# lp4200.net
KiCad netlist of a schematic drawn in Altium Designer
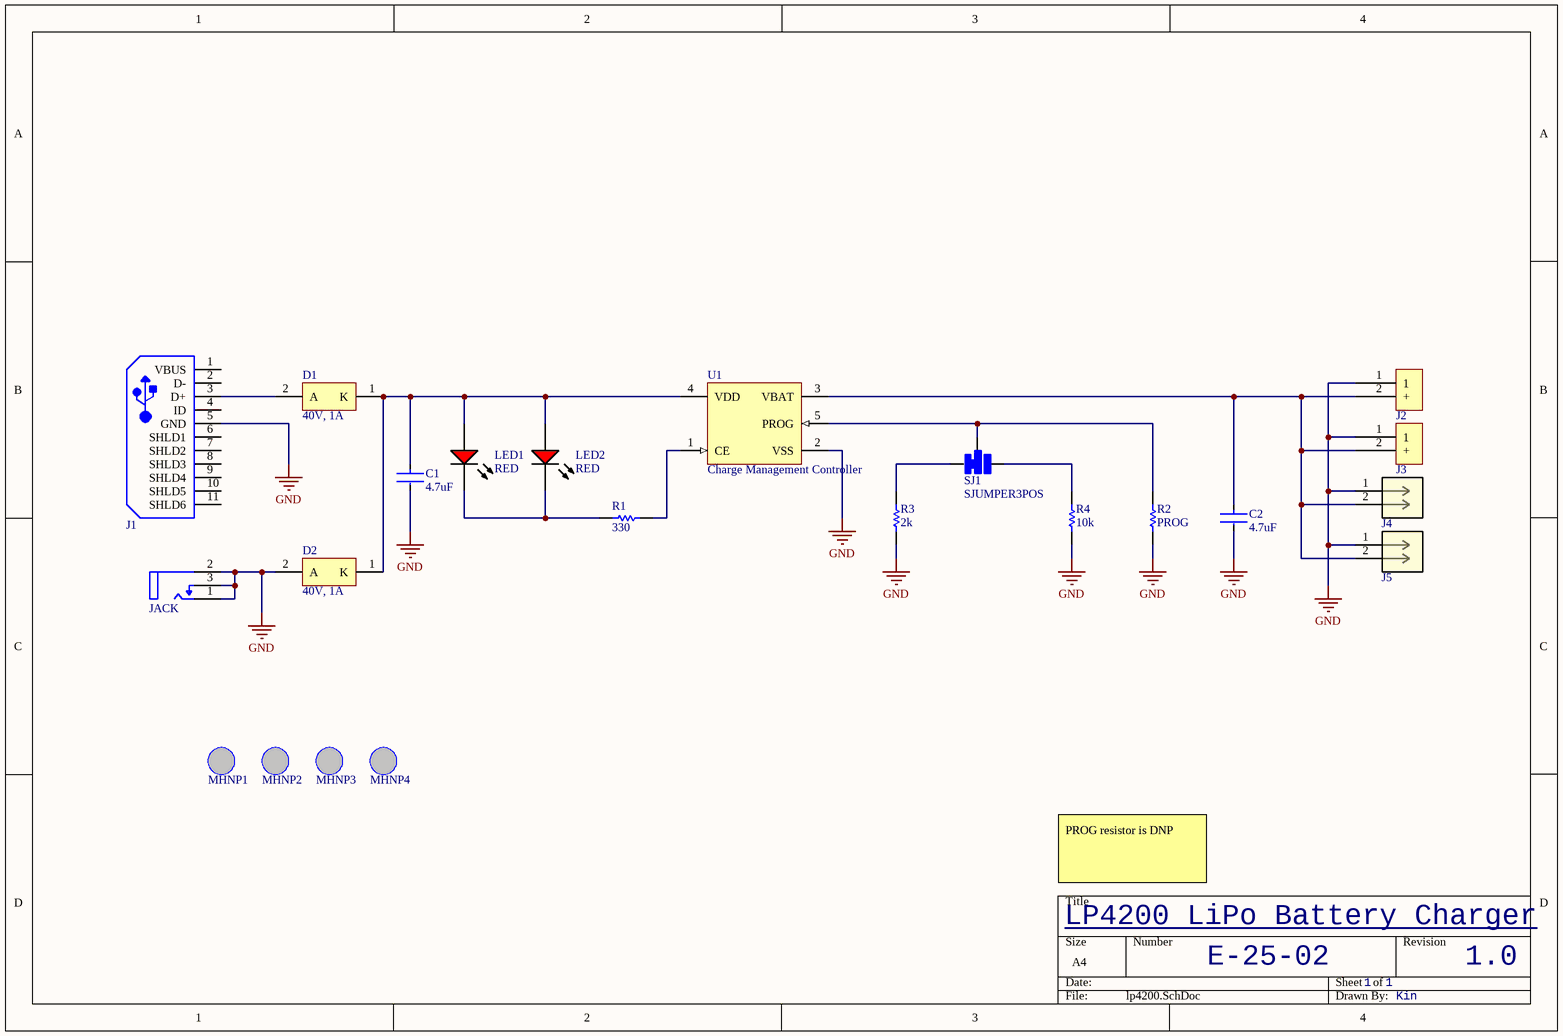
[diagram p0: lp4200.SchDoc]

(export (version "E")
  (design (tool "Eeschema 10.0.6"))
  (components
    (comp (ref "C1")
      (value "4.7uF")
      (footprint "FP-CC0805-0_85-MFG")
      (description "4.7µF ±10% 6.3V Ceramic Capacitor X7R 0805 (2012 Metric)")
      (fields (field (name "MANUFACTURER") "Yageo") (field (name "TOLERANCE") "0.1"))
      (libsource (lib "lp4200") (part "CAP CER 4.7UF 6.3V X7R 0805"))
    )
    (comp (ref "C2")
      (value "4.7uF")
      (footprint "FP-CC0805-0_85-MFG")
      (description "4.7µF ±10% 6.3V Ceramic Capacitor X7R 0805 (2012 Metric)")
      (fields (field (name "MANUFACTURER") "Yageo") (field (name "TOLERANCE") "0.1"))
      (libsource (lib "lp4200") (part "CAP CER 4.7UF 6.3V X7R 0805"))
    )
    (comp (ref "D1")
      (value "40V, 1A")
      (footprint "ONSC-SMA-2-403D-02_V")
      (description "Schottky Power Rectifier, 2-Pin SMA, Pb-Free, Cut Tape, Diode Schottky 40V 1A Surface Mount SMA")
      (fields (field (name "PARTNUMBER") "MBRA140T3G") (field (name "MANUFACTURER") "ON Semiconductor"))
      (libsource (lib "lp4200") (part "DIODE SCHOTTKY 40V 1A SMA"))
    )
    (comp (ref "D2")
      (value "40V, 1A")
      (footprint "ONSC-SMA-2-403D-02_V")
      (description "Schottky Power Rectifier, 2-Pin SMA, Pb-Free, Cut Tape, Diode Schottky 40V 1A Surface Mount SMA")
      (fields (field (name "PARTNUMBER") "MBRA140T3G") (field (name "MANUFACTURER") "ON Semiconductor"))
      (libsource (lib "lp4200") (part "DIODE SCHOTTKY 40V 1A SMA"))
    )
    (comp (ref "J1")
      (value "47346-0001")
      (footprint "MOLX-47346-0001-5_V")
      (description "Micro-USB B Receptacle with Flange, -30 to 85 degC, 5-Pin SMD, RoHS, Tape and Reel")
      (fields (field (name "MANUFACTURER") "Molex"))
      (libsource (lib "lp4200") (part "CONN RCPT USB2.0 MICRO B SMD R/A"))
    )
    (comp (ref "J2")
      (value "CONN HEADER R/A 2POS 5.08MM")
      (footprint "1-179276-2")
      (description "Connector Header Through Hole, Right Angle 2 position 0.200\" (5.08mm)")
      (fields
        (field (name "MANUFACTURER") "TE Connectivity AMP Connectors")
        (field (name "MANUFACTURER PART NUMBER") "1-179276-2")
      )
      (libsource (lib "lp4200") (part "CONN HEADER R/A 2POS 5.08MM"))
    )
    (comp (ref "J3")
      (value "CONN HEADER R/A 2POS 5.08MM")
      (footprint "1-179276-2")
      (description "Connector Header Through Hole, Right Angle 2 position 0.200\" (5.08mm)")
      (fields
        (field (name "MANUFACTURER") "TE Connectivity AMP Connectors")
        (field (name "MANUFACTURER PART NUMBER") "1-179276-2")
      )
      (libsource (lib "lp4200") (part "CONN HEADER R/A 2POS 5.08MM"))
    )
    (comp (ref "J4")
      (value "2 POS VERT HEADER 0.100\"")
      (footprint "2Pins_AMP")
      (description "Connector Header Through Hole 2 position")
      (fields
        (field (name "MANUFACTURER PART NUMBER") "67997-402HLF")
        (field (name "MANUFACTURER") "Amphenol ICC (FCI)")
        (field (name "COPYRIGHT") "Copyright (C) 2018 Accelerated Designs. All rights reserved")
      )
      (libsource (lib "lp4200") (part "CONN HEADER VERT 2POS 0.100{dblquote}"))
    )
    (comp (ref "J5")
      (value "2 POS VERT HEADER 0.100\"")
      (footprint "2Pins_AMP")
      (description "Connector Header Through Hole 2 position")
      (fields
        (field (name "MANUFACTURER PART NUMBER") "67997-402HLF")
        (field (name "MANUFACTURER") "Amphenol ICC (FCI)")
        (field (name "COPYRIGHT") "Copyright (C) 2018 Accelerated Designs. All rights reserved")
      )
      (libsource (lib "lp4200") (part "CONN HEADER VERT 2POS 0.100{dblquote}"))
    )
    (comp (ref "JACK")
      (value "CONN PWR JACK 2.1X5.5MM SOLDER")
      (footprint "FP-RASM722PTR13X-MFG")
      (description "Power Barrel Connector Jack 2.10mm ID (0.083\"), 5.50mm OD (0.217\") Surface Mount, Right Angle")
      (fields
        (field (name "MANUFACTURER") "Switchcraft")
        (field (name "MANUFACTURER PART NUMBER") "RASM722PTR13X")
      )
      (libsource (lib "lp4200") (part "CONN PWR JACK 2.1X5.5MM SOLDER"))
    )
    (comp (ref "LED1")
      (value "RED")
      (footprint "VISH-TLMS1000_V")
      (description "Low Current LED, 40 mW, 1.8 V, -40 to 100 degC, 2-Pin SMD (0603), RoHS, Tape and Reel")
      (fields
        (field (name "MANUFACTURER") "Vishay")
        (field (name "MANUFACTURER PART NUMBER") "TLMS1000-GS08")
      )
      (libsource (lib "lp4200") (part "LED RED 0603 SMD"))
    )
    (comp (ref "LED2")
      (value "RED")
      (footprint "VISH-TLMS1000_V")
      (description "Low Current LED, 40 mW, 1.8 V, -40 to 100 degC, 2-Pin SMD (0603), RoHS, Tape and Reel")
      (fields
        (field (name "MANUFACTURER") "Vishay")
        (field (name "MANUFACTURER PART NUMBER") "TLMS1000-GS08")
      )
      (libsource (lib "lp4200") (part "LED RED 0603 SMD"))
    )
    (comp (ref "MHNP1")
      (value "Mounting Hole Non-Plated 3.2mm")
      (footprint "MTHNP3P2MM")
      (description "Mounting Hole Non-Plated 3.2 mm drill hole")
      (libsource (lib "lp4200") (part "MTHNP3P2MM"))
    )
    (comp (ref "MHNP2")
      (value "Mounting Hole Non-Plated 3.2mm")
      (footprint "MTHNP3P2MM")
      (description "Mounting Hole Non-Plated 3.2 mm drill hole")
      (libsource (lib "lp4200") (part "MTHNP3P2MM"))
    )
    (comp (ref "MHNP3")
      (value "Mounting Hole Non-Plated 3.2mm")
      (footprint "MTHNP3P2MM")
      (description "Mounting Hole Non-Plated 3.2 mm drill hole")
      (libsource (lib "lp4200") (part "MTHNP3P2MM"))
    )
    (comp (ref "MHNP4")
      (value "Mounting Hole Non-Plated 3.2mm")
      (footprint "MTHNP3P2MM")
      (description "Mounting Hole Non-Plated 3.2 mm drill hole")
      (libsource (lib "lp4200") (part "MTHNP3P2MM"))
    )
    (comp (ref "R1")
      (value "330")
      (footprint "RESC2013X50X30NL20T20")
      (description "330 Ohms ±1% 0.125W, 1/8W Chip Resistor 0805 (2012 Metric) Automotive AEC-Q200 Thick Film")
      (fields
        (field (name "MANUFACTURER") "Vishay")
        (field (name "MANUFACTURER PART NUMBER") "CRCW0805330RFKEA")
      )
      (libsource (lib "lp4200") (part "RES SMD 330 OHM 1% 1/8W 0805"))
    )
    (comp (ref "R2")
      (value "PROG")
      (footprint "VISH-A1-2_V2")
      (fields
        (field (name "TOLERANCE") "+/-5%")
        (field (name "POWER") "2 W")
        (field (name "PARTNUMBER") "PR02000206202JA100")
      )
      (libsource (lib "lp4200") (part "RES 62K OHM 2W 5% AXIAL"))
    )
    (comp (ref "R3")
      (value "2k")
      (footprint "RESC2013X70X40ML20T20")
      (description "2 kOhms ±5% 0.125W, 1/8W Chip Resistor 0805 (2012 Metric) Automotive AEC-Q200 Thick Film")
      (fields
        (field (name "MANUFACTURER") "Panasonic")
        (field (name "MANUFACTURER PART NUMBER") "ERJ-6GEYJ202V")
      )
      (libsource (lib "lp4200") (part "RES SMD 2K OHM 5% 1/8W 0805"))
    )
    (comp (ref "R4")
      (value "10k")
      (footprint "RESC2013X70X40ML20T20")
      (description "10 kOhms ±1% 0.125W, 1/8W Chip Resistor 0805 (2012 Metric) Automotive AEC-Q200 Thick Film")
      (fields
        (field (name "MANUFACTURER") "Panasonic")
        (field (name "MANUFACTURER PART NUMBER") "ERJ-6ENF1002V")
      )
      (libsource (lib "lp4200") (part "RES SMD 10K OHM 1% 1/8W 0805"))
    )
    (comp (ref "SJ1")
      (value "SJUMPER3POS")
      (footprint "SJUMPER3POS-Footprint-1")
      (description "Solder jumper 3 pads and pins")
      (libsource (lib "lp4200") (part "SJUMPER3POS"))
    )
    (comp (ref "U1")
      (value "Charge Management Controller")
      (footprint "SOT-23-OT5_M")
      (fields
        (field (name "MANUFACTURER") "Microchip")
        (field (name "MANUFACTURER PART NUMBER") "MCP73811T-420I/OT")
      )
      (libsource (lib "lp4200") (part "IC LI-ION/LI-POLY CTRLR SOT23-5"))
    )
  )
  (nets
    (net (code "1") (name "GND") (class "Default")
      (node (ref "C1") (pin "2") (pinfunction "2_2") (pintype "passive"))
      (node (ref "C2") (pin "2") (pinfunction "2_2") (pintype "passive"))
      (node (ref "D2") (pin "2") (pinfunction "A_2") (pintype "passive"))
      (node (ref "J1") (pin "5") (pinfunction "GND_5") (pintype "passive"))
      (node (ref "J2") (pin "1") (pinfunction "1_1") (pintype "passive"))
      (node (ref "J3") (pin "1") (pinfunction "1_1") (pintype "passive"))
      (node (ref "J4") (pin "1") (pinfunction "1_1") (pintype "passive"))
      (node (ref "J5") (pin "1") (pinfunction "1_1") (pintype "passive"))
      (node (ref "JACK") (pin "1") (pinfunction "TIP_TERMINAL(CENTER_PIN)_1") (pintype "passive"))
      (node (ref "JACK") (pin "2") (pinfunction "SLEEVE_TERMINAL_2") (pintype "passive"))
      (node (ref "JACK") (pin "3") (pinfunction "SHUNT_TERMINAL_3") (pintype "passive"))
      (node (ref "R2") (pin "1") (pinfunction "1_1") (pintype "passive"))
      (node (ref "R3") (pin "1") (pinfunction "1_1") (pintype "passive"))
      (node (ref "R4") (pin "1") (pinfunction "1_1") (pintype "passive"))
      (node (ref "U1") (pin "2") (pinfunction "VSS_2") (pintype "power_in"))
    )
    (net (code "2") (name "Net-(D1-A)") (class "Default")
      (node (ref "D1") (pin "2") (pinfunction "A_2") (pintype "passive"))
      (node (ref "J1") (pin "3") (pinfunction "D+_3") (pintype "passive"))
    )
    (net (code "3") (name "Net-(D1-K)") (class "Default")
      (node (ref "C1") (pin "1") (pinfunction "1_1") (pintype "passive"))
      (node (ref "D1") (pin "1") (pinfunction "K_1") (pintype "passive"))
      (node (ref "D2") (pin "1") (pinfunction "K_1") (pintype "passive"))
      (node (ref "LED1") (pin "1") (pinfunction "A_1") (pintype "passive"))
      (node (ref "LED2") (pin "1") (pinfunction "A_1") (pintype "passive"))
      (node (ref "U1") (pin "4") (pinfunction "VDD_4") (pintype "power_in"))
    )
    (net (code "4") (name "Net-(J2-+)") (class "Default")
      (node (ref "C2") (pin "1") (pinfunction "1_1") (pintype "passive"))
      (node (ref "J2") (pin "2") (pinfunction "+_2") (pintype "passive"))
      (node (ref "J3") (pin "2") (pinfunction "+_2") (pintype "passive"))
      (node (ref "J4") (pin "2") (pinfunction "2_2") (pintype "passive"))
      (node (ref "J5") (pin "2") (pinfunction "2_2") (pintype "passive"))
      (node (ref "U1") (pin "3") (pinfunction "VBAT_3") (pintype "power_in"))
    )
    (net (code "5") (name "Net-(LED1-K)") (class "Default")
      (node (ref "LED1") (pin "2") (pinfunction "K_2") (pintype "passive"))
      (node (ref "LED2") (pin "2") (pinfunction "K_2") (pintype "passive"))
      (node (ref "R1") (pin "1") (pinfunction "1_1") (pintype "passive"))
    )
    (net (code "6") (name "Net-(R3-Pad2)") (class "Default")
      (node (ref "R3") (pin "2") (pinfunction "2_2") (pintype "passive"))
      (node (ref "SJ1") (pin "1") (pinfunction "1_1") (pintype "passive"))
    )
    (net (code "7") (name "Net-(R4-Pad2)") (class "Default")
      (node (ref "R4") (pin "2") (pinfunction "2_2") (pintype "passive"))
      (node (ref "SJ1") (pin "3") (pinfunction "3_3") (pintype "passive"))
    )
    (net (code "8") (name "Net-(U1-CE)") (class "Default")
      (node (ref "R1") (pin "2") (pinfunction "2_2") (pintype "passive"))
      (node (ref "U1") (pin "1") (pinfunction "CE_1") (pintype "input"))
    )
    (net (code "9") (name "Net-(U1-PROG)") (class "Default")
      (node (ref "R2") (pin "2") (pinfunction "2_2") (pintype "passive"))
      (node (ref "SJ1") (pin "2") (pinfunction "2_2") (pintype "passive"))
      (node (ref "U1") (pin "5") (pinfunction "PROG_5") (pintype "input"))
    )
    (net (code "10") (name "unconnected-(J1-D--Pad2)") (class "Default")
      (node (ref "J1") (pin "2") (pinfunction "D-_2") (pintype "passive"))
    )
    (net (code "11") (name "unconnected-(J1-ID-Pad4)") (class "Default")
      (node (ref "J1") (pin "4") (pinfunction "ID_4") (pintype "passive"))
    )
    (net (code "12") (name "unconnected-(J1-SHLD1-Pad6)") (class "Default")
      (node (ref "J1") (pin "6") (pinfunction "SHLD1_6") (pintype "passive"))
    )
    (net (code "13") (name "unconnected-(J1-SHLD2-Pad7)") (class "Default")
      (node (ref "J1") (pin "7") (pinfunction "SHLD2_7") (pintype "passive"))
    )
    (net (code "14") (name "unconnected-(J1-SHLD3-Pad8)") (class "Default")
      (node (ref "J1") (pin "8") (pinfunction "SHLD3_8") (pintype "passive"))
    )
    (net (code "15") (name "unconnected-(J1-SHLD4-Pad9)") (class "Default")
      (node (ref "J1") (pin "9") (pinfunction "SHLD4_9") (pintype "passive"))
    )
    (net (code "16") (name "unconnected-(J1-SHLD5-Pad10)") (class "Default")
      (node (ref "J1") (pin "10") (pinfunction "SHLD5_10") (pintype "passive"))
    )
    (net (code "17") (name "unconnected-(J1-SHLD6-Pad11)") (class "Default")
      (node (ref "J1") (pin "11") (pinfunction "SHLD6_11") (pintype "passive"))
    )
    (net (code "18") (name "unconnected-(J1-VBUS-Pad1)") (class "Default")
      (node (ref "J1") (pin "1") (pinfunction "VBUS_1") (pintype "passive"))
    )
  )
)
